# RiseUpBOTTOM.net
KiCad netlist of a schematic drawn in EAGLE
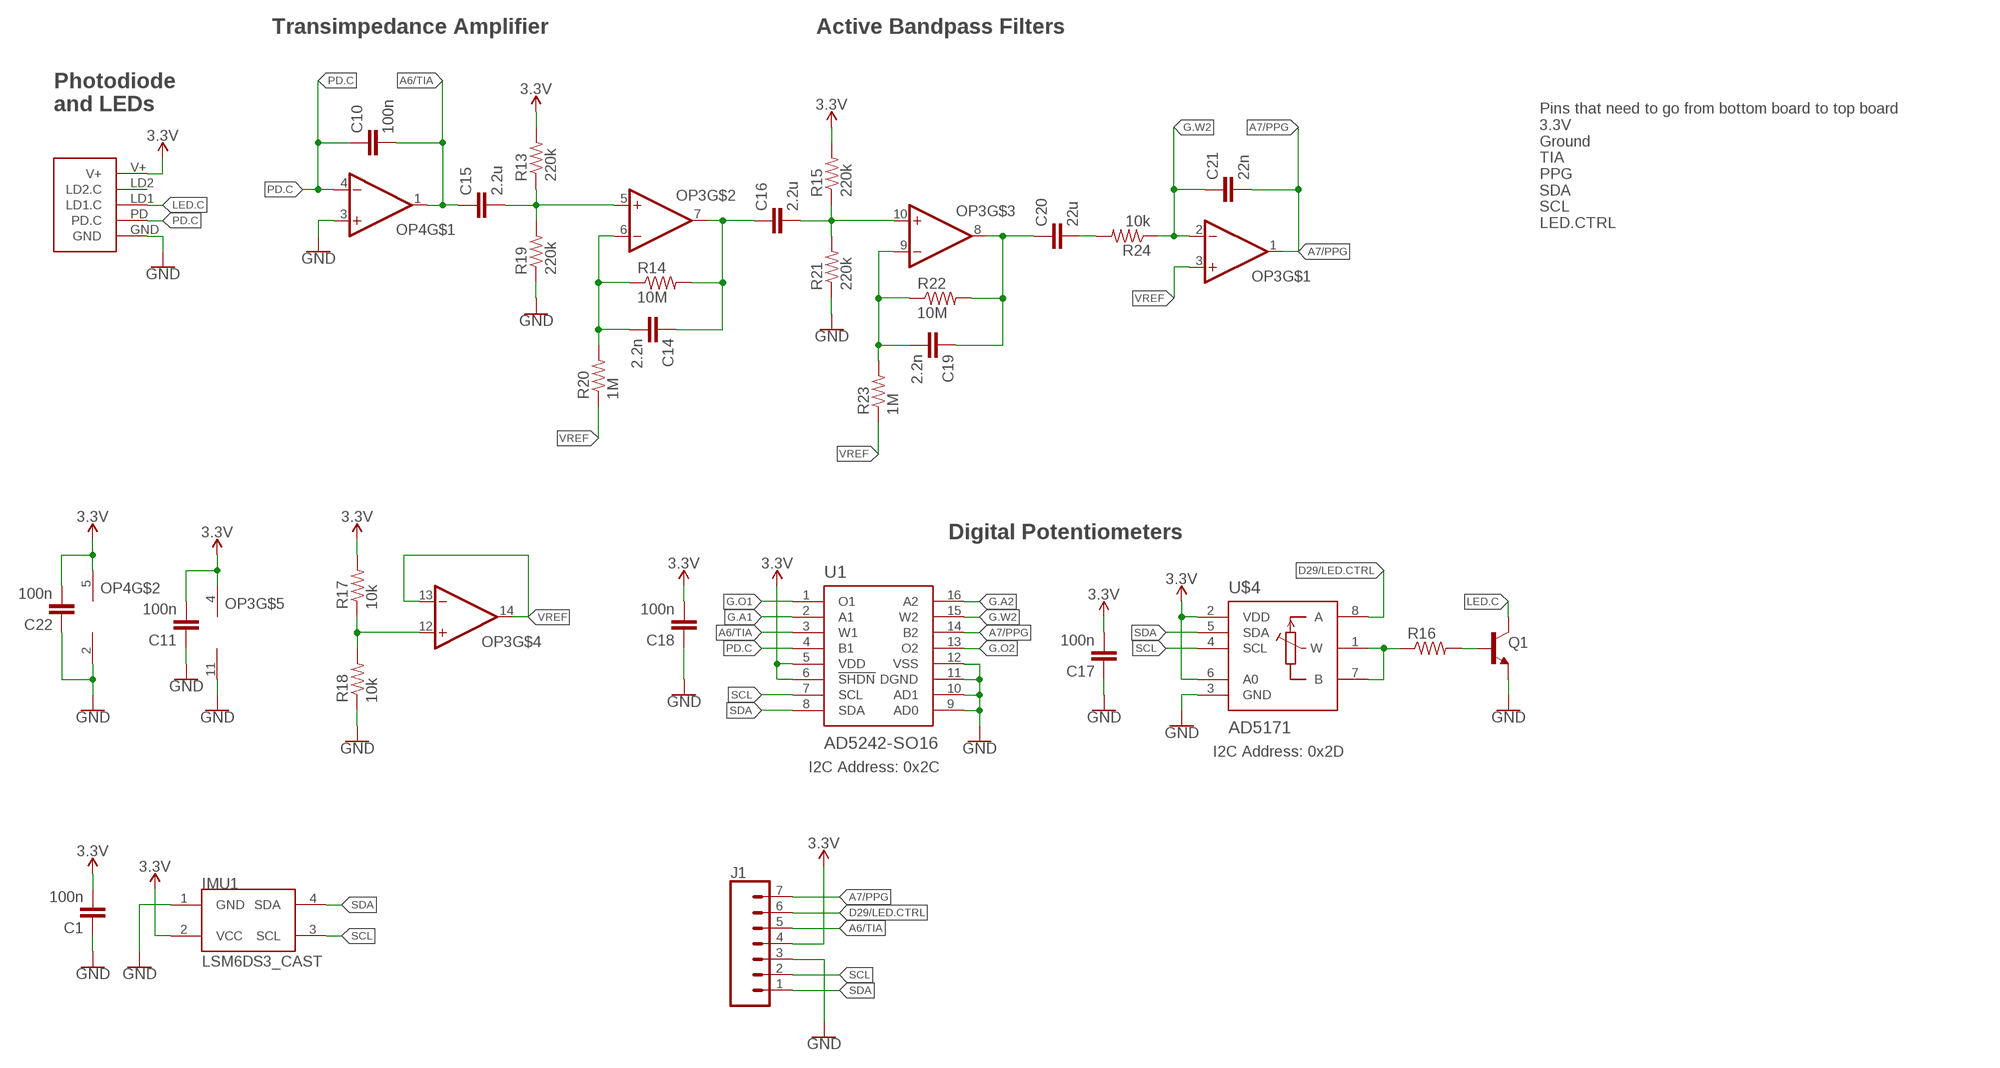
[diagram p0: schematic, sheet 1]

(export (version "E")
  (design (tool "Eeschema 10.0.6"))
  (components
    (comp (ref "C1")
      (value "100n")
      (footprint "eagle-import:C0603")
      (libsource (lib "eagle-import") (part "CAPACITOR0603"))
    )
    (comp (ref "C10")
      (value "100n")
      (footprint "eagle-import:C0603")
      (libsource (lib "eagle-import") (part "CAPACITOR0603"))
    )
    (comp (ref "C11")
      (value "100n")
      (footprint "eagle-import:C0603")
      (libsource (lib "eagle-import") (part "CAPACITOR0603"))
    )
    (comp (ref "C14")
      (value "2.2n")
      (footprint "eagle-import:C0603")
      (libsource (lib "eagle-import") (part "CAPACITOR0603"))
    )
    (comp (ref "C15")
      (value "2.2u")
      (footprint "eagle-import:C0603")
      (libsource (lib "eagle-import") (part "CAPACITOR0603"))
    )
    (comp (ref "C16")
      (value "2.2u")
      (footprint "eagle-import:C0603")
      (libsource (lib "eagle-import") (part "CAPACITOR0603"))
    )
    (comp (ref "C17")
      (value "100n")
      (footprint "eagle-import:C0603")
      (libsource (lib "eagle-import") (part "CAPACITOR0603"))
    )
    (comp (ref "C18")
      (value "100n")
      (footprint "eagle-import:C0603")
      (libsource (lib "eagle-import") (part "CAPACITOR0603"))
    )
    (comp (ref "C19")
      (value "2.2n")
      (footprint "eagle-import:C0603")
      (libsource (lib "eagle-import") (part "CAPACITOR0603"))
    )
    (comp (ref "C20")
      (value "22u")
      (footprint "eagle-import:C0603")
      (libsource (lib "eagle-import") (part "CAPACITOR0603"))
    )
    (comp (ref "C21")
      (value "22n")
      (footprint "eagle-import:C0603")
      (libsource (lib "eagle-import") (part "CAPACITOR0603"))
    )
    (comp (ref "C22")
      (value "100n")
      (footprint "eagle-import:C0603")
      (libsource (lib "eagle-import") (part "CAPACITOR0603"))
    )
    (comp (ref "IMU1")
      (value "LSM6DS3_CAST")
      (footprint "eagle-import:LSM6DS3_CAST")
      (libsource (lib "eagle-import") (part "LSM6DS3_CAST"))
    )
    (comp (ref "J1")
      (value "CONN_07")
      (footprint "eagle-import:1X07")
      (libsource (lib "eagle-import") (part "CONN_07"))
    )
    (comp (ref "OP3")
      (value "OP-QUAD-SO14")
      (footprint "eagle-import:SO14")
      (libsource (lib "eagle-import") (part "OP-QUAD-SO14"))
    )
    (comp (ref "OP4")
      (value "OP-SINGLEOT")
      (footprint "eagle-import:SOT23-5")
      (libsource (lib "eagle-import") (part "OP-SINGLEOT"))
    )
    (comp (ref "Q1")
      (value "NPN-GENERIC")
      (footprint "eagle-import:SOT23-3")
      (libsource (lib "eagle-import") (part "NPN-GENERIC"))
    )
    (comp (ref "R13")
      (value "220k")
      (footprint "eagle-import:R0603")
      (libsource (lib "eagle-import") (part "RESISTOR0603"))
    )
    (comp (ref "R14")
      (value "10M")
      (footprint "eagle-import:R0603")
      (libsource (lib "eagle-import") (part "RESISTOR0603"))
    )
    (comp (ref "R15")
      (value "220k")
      (footprint "eagle-import:R0603")
      (libsource (lib "eagle-import") (part "RESISTOR0603"))
    )
    (comp (ref "R16")
      (value "RESISTOR0603")
      (footprint "eagle-import:R0603")
      (libsource (lib "eagle-import") (part "RESISTOR0603"))
    )
    (comp (ref "R17")
      (value "10k")
      (footprint "eagle-import:R0402")
      (libsource (lib "eagle-import") (part "RESISTOR0402"))
    )
    (comp (ref "R18")
      (value "10k")
      (footprint "eagle-import:R0402")
      (libsource (lib "eagle-import") (part "RESISTOR0402"))
    )
    (comp (ref "R19")
      (value "220k")
      (footprint "eagle-import:R0603")
      (libsource (lib "eagle-import") (part "RESISTOR0603"))
    )
    (comp (ref "R20")
      (value "1M")
      (footprint "eagle-import:R0603")
      (libsource (lib "eagle-import") (part "RESISTOR0603"))
    )
    (comp (ref "R21")
      (value "220k")
      (footprint "eagle-import:R0603")
      (libsource (lib "eagle-import") (part "RESISTOR0603"))
    )
    (comp (ref "R22")
      (value "10M")
      (footprint "eagle-import:R0603")
      (libsource (lib "eagle-import") (part "RESISTOR0603"))
    )
    (comp (ref "R23")
      (value "1M")
      (footprint "eagle-import:R0603")
      (libsource (lib "eagle-import") (part "RESISTOR0603"))
    )
    (comp (ref "R24")
      (value "10k")
      (footprint "eagle-import:R0603")
      (libsource (lib "eagle-import") (part "RESISTOR0603"))
    )
    (comp (ref "U$3")
      (value "PPG.MODULE.2")
      (footprint "eagle-import:PPG.MODULE.2")
      (libsource (lib "eagle-import") (part "PPG.MODULE.2"))
    )
    (comp (ref "U$4")
      (value "AD5171")
      (footprint "eagle-import:SOT-23-8")
      (libsource (lib "eagle-import") (part "AD5171"))
    )
    (comp (ref "U1")
      (value "AD5242-SO16")
      (footprint "eagle-import:SO16")
      (libsource (lib "eagle-import") (part "AD5242-SO16"))
    )
  )
  (nets
    (net (code "1") (name "3.3V") (class "Default")
      (node (ref "C1") (pin "2") (pinfunction "2_2") (pintype "passive"))
      (node (ref "C11") (pin "2") (pinfunction "2_2") (pintype "passive"))
      (node (ref "C17") (pin "2") (pinfunction "2_2") (pintype "passive"))
      (node (ref "C18") (pin "2") (pinfunction "2_2") (pintype "passive"))
      (node (ref "C22") (pin "2") (pinfunction "2_2") (pintype "passive"))
      (node (ref "IMU1") (pin "2") (pinfunction "VCC_2") (pintype "bidirectional"))
      (node (ref "J1") (pin "4") (pinfunction "4_4") (pintype "passive"))
      (node (ref "OP3") (pin "4") (pinfunction "V+_4") (pintype "power_in"))
      (node (ref "OP4") (pin "5") (pinfunction "V+_5") (pintype "power_in"))
      (node (ref "R13") (pin "2") (pinfunction "2_2") (pintype "passive"))
      (node (ref "R15") (pin "2") (pinfunction "2_2") (pintype "passive"))
      (node (ref "R17") (pin "2") (pinfunction "2_2") (pintype "passive"))
      (node (ref "U$3") (pin "V+") (pinfunction "V+_V+") (pintype "bidirectional"))
      (node (ref "U$4") (pin "2") (pinfunction "VDD_2") (pintype "bidirectional"))
      (node (ref "U$4") (pin "6") (pinfunction "A0_6") (pintype "bidirectional"))
      (node (ref "U1") (pin "5") (pinfunction "VDD_5") (pintype "bidirectional"))
      (node (ref "U1") (pin "6") (pinfunction "~{SHDN}_6") (pintype "bidirectional"))
    )
    (net (code "2") (name "A6{slash}TIA") (class "Default")
      (node (ref "C10") (pin "2") (pinfunction "2_2") (pintype "passive"))
      (node (ref "C15") (pin "1") (pinfunction "1_1") (pintype "passive"))
      (node (ref "J1") (pin "5") (pinfunction "5_5") (pintype "passive"))
      (node (ref "OP4") (pin "1") (pinfunction "OUT_1") (pintype "output"))
      (node (ref "U1") (pin "3") (pinfunction "W1_3") (pintype "bidirectional"))
    )
    (net (code "3") (name "A7{slash}PPG") (class "Default")
      (node (ref "C21") (pin "2") (pinfunction "2_2") (pintype "passive"))
      (node (ref "J1") (pin "7") (pinfunction "7_7") (pintype "passive"))
      (node (ref "OP3") (pin "1") (pinfunction "OUT_1") (pintype "output"))
      (node (ref "U1") (pin "14") (pinfunction "B2_14") (pintype "bidirectional"))
    )
    (net (code "4") (name "D29{slash}LED.CTRL") (class "Default")
      (node (ref "J1") (pin "6") (pinfunction "6_6") (pintype "passive"))
      (node (ref "U$4") (pin "8") (pinfunction "A_8") (pintype "bidirectional"))
    )
    (net (code "5") (name "G.A1") (class "Default")
      (node (ref "U1") (pin "2") (pinfunction "A1_2") (pintype "bidirectional"))
    )
    (net (code "6") (name "G.A2") (class "Default")
      (node (ref "U1") (pin "16") (pinfunction "A2_16") (pintype "bidirectional"))
    )
    (net (code "7") (name "G.O1") (class "Default")
      (node (ref "U1") (pin "1") (pinfunction "O1_1") (pintype "bidirectional"))
    )
    (net (code "8") (name "G.O2") (class "Default")
      (node (ref "U1") (pin "13") (pinfunction "O2_13") (pintype "bidirectional"))
    )
    (net (code "9") (name "G.W2") (class "Default")
      (node (ref "C21") (pin "1") (pinfunction "1_1") (pintype "passive"))
      (node (ref "OP3") (pin "2") (pinfunction "-IN_2") (pintype "input"))
      (node (ref "R24") (pin "1") (pinfunction "1_1") (pintype "passive"))
      (node (ref "U1") (pin "15") (pinfunction "W2_15") (pintype "bidirectional"))
    )
    (net (code "10") (name "GND") (class "Default")
      (node (ref "C1") (pin "1") (pinfunction "1_1") (pintype "passive"))
      (node (ref "C11") (pin "1") (pinfunction "1_1") (pintype "passive"))
      (node (ref "C17") (pin "1") (pinfunction "1_1") (pintype "passive"))
      (node (ref "C18") (pin "1") (pinfunction "1_1") (pintype "passive"))
      (node (ref "C22") (pin "1") (pinfunction "1_1") (pintype "passive"))
      (node (ref "IMU1") (pin "1") (pinfunction "GND_1") (pintype "bidirectional"))
      (node (ref "J1") (pin "3") (pinfunction "3_3") (pintype "passive"))
      (node (ref "OP3") (pin "11") (pinfunction "V-_11") (pintype "power_in"))
      (node (ref "OP4") (pin "2") (pinfunction "V-_2") (pintype "power_in"))
      (node (ref "OP4") (pin "3") (pinfunction "+IN_3") (pintype "input"))
      (node (ref "Q1") (pin "2") (pinfunction "E_2") (pintype "passive"))
      (node (ref "R18") (pin "1") (pinfunction "1_1") (pintype "passive"))
      (node (ref "R19") (pin "1") (pinfunction "1_1") (pintype "passive"))
      (node (ref "R21") (pin "1") (pinfunction "1_1") (pintype "passive"))
      (node (ref "U$3") (pin "GND") (pinfunction "GND_GND") (pintype "bidirectional"))
      (node (ref "U$4") (pin "3") (pinfunction "GND_3") (pintype "bidirectional"))
      (node (ref "U1") (pin "10") (pinfunction "AD1_10") (pintype "bidirectional"))
      (node (ref "U1") (pin "11") (pinfunction "DGND_11") (pintype "bidirectional"))
      (node (ref "U1") (pin "12") (pinfunction "VSS_12") (pintype "bidirectional"))
      (node (ref "U1") (pin "9") (pinfunction "AD0_9") (pintype "bidirectional"))
    )
    (net (code "11") (name "LED.C") (class "Default")
      (node (ref "Q1") (pin "3") (pinfunction "C_3") (pintype "passive"))
      (node (ref "U$3") (pin "LD1") (pinfunction "LD1.C_LD1") (pintype "bidirectional"))
    )
    (net (code "12") (name "Net-(C20-Pad2)") (class "Default")
      (node (ref "C20") (pin "2") (pinfunction "2_2") (pintype "passive"))
      (node (ref "R24") (pin "2") (pinfunction "2_2") (pintype "passive"))
    )
    (net (code "13") (name "Net-(OP3B-+IN)") (class "Default")
      (node (ref "C15") (pin "2") (pinfunction "2_2") (pintype "passive"))
      (node (ref "OP3") (pin "5") (pinfunction "+IN_5") (pintype "input"))
      (node (ref "R13") (pin "1") (pinfunction "1_1") (pintype "passive"))
      (node (ref "R19") (pin "2") (pinfunction "2_2") (pintype "passive"))
    )
    (net (code "14") (name "Net-(OP3B--IN)") (class "Default")
      (node (ref "C14") (pin "2") (pinfunction "2_2") (pintype "passive"))
      (node (ref "OP3") (pin "6") (pinfunction "-IN_6") (pintype "input"))
      (node (ref "R14") (pin "1") (pinfunction "1_1") (pintype "passive"))
      (node (ref "R20") (pin "2") (pinfunction "2_2") (pintype "passive"))
    )
    (net (code "15") (name "Net-(OP3B-OUT)") (class "Default")
      (node (ref "C14") (pin "1") (pinfunction "1_1") (pintype "passive"))
      (node (ref "C16") (pin "1") (pinfunction "1_1") (pintype "passive"))
      (node (ref "OP3") (pin "7") (pinfunction "OUT_7") (pintype "output"))
      (node (ref "R14") (pin "2") (pinfunction "2_2") (pintype "passive"))
    )
    (net (code "16") (name "Net-(OP3C-+IN)") (class "Default")
      (node (ref "C16") (pin "2") (pinfunction "2_2") (pintype "passive"))
      (node (ref "OP3") (pin "10") (pinfunction "+IN_10") (pintype "input"))
      (node (ref "R15") (pin "1") (pinfunction "1_1") (pintype "passive"))
      (node (ref "R21") (pin "2") (pinfunction "2_2") (pintype "passive"))
    )
    (net (code "17") (name "Net-(OP3C--IN)") (class "Default")
      (node (ref "C19") (pin "2") (pinfunction "2_2") (pintype "passive"))
      (node (ref "OP3") (pin "9") (pinfunction "-IN_9") (pintype "input"))
      (node (ref "R22") (pin "1") (pinfunction "1_1") (pintype "passive"))
      (node (ref "R23") (pin "2") (pinfunction "2_2") (pintype "passive"))
    )
    (net (code "18") (name "Net-(OP3C-OUT)") (class "Default")
      (node (ref "C19") (pin "1") (pinfunction "1_1") (pintype "passive"))
      (node (ref "C20") (pin "1") (pinfunction "1_1") (pintype "passive"))
      (node (ref "OP3") (pin "8") (pinfunction "OUT_8") (pintype "output"))
      (node (ref "R22") (pin "2") (pinfunction "2_2") (pintype "passive"))
    )
    (net (code "19") (name "Net-(OP3D-+IN)") (class "Default")
      (node (ref "OP3") (pin "12") (pinfunction "+IN_12") (pintype "input"))
      (node (ref "R17") (pin "1") (pinfunction "1_1") (pintype "passive"))
      (node (ref "R18") (pin "2") (pinfunction "2_2") (pintype "passive"))
    )
    (net (code "20") (name "Net-(Q1-B)") (class "Default")
      (node (ref "Q1") (pin "1") (pinfunction "B_1") (pintype "passive"))
      (node (ref "R16") (pin "2") (pinfunction "2_2") (pintype "passive"))
    )
    (net (code "21") (name "Net-(U$4-B)") (class "Default")
      (node (ref "R16") (pin "1") (pinfunction "1_1") (pintype "passive"))
      (node (ref "U$4") (pin "1") (pinfunction "W_1") (pintype "bidirectional"))
      (node (ref "U$4") (pin "7") (pinfunction "B_7") (pintype "bidirectional"))
    )
    (net (code "22") (name "PD.C") (class "Default")
      (node (ref "C10") (pin "1") (pinfunction "1_1") (pintype "passive"))
      (node (ref "OP4") (pin "4") (pinfunction "-IN_4") (pintype "input"))
      (node (ref "U$3") (pin "PD") (pinfunction "PD.C_PD") (pintype "bidirectional"))
      (node (ref "U1") (pin "4") (pinfunction "B1_4") (pintype "bidirectional"))
    )
    (net (code "23") (name "SCL") (class "Default")
      (node (ref "IMU1") (pin "3") (pinfunction "SCL_3") (pintype "bidirectional"))
      (node (ref "J1") (pin "2") (pinfunction "2_2") (pintype "passive"))
      (node (ref "U$4") (pin "4") (pinfunction "SCL_4") (pintype "bidirectional"))
      (node (ref "U1") (pin "7") (pinfunction "SCL_7") (pintype "bidirectional"))
    )
    (net (code "24") (name "SDA") (class "Default")
      (node (ref "IMU1") (pin "4") (pinfunction "SDA_4") (pintype "bidirectional"))
      (node (ref "J1") (pin "1") (pinfunction "1_1") (pintype "passive"))
      (node (ref "U$4") (pin "5") (pinfunction "SDA_5") (pintype "bidirectional"))
      (node (ref "U1") (pin "8") (pinfunction "SDA_8") (pintype "bidirectional"))
    )
    (net (code "25") (name "VREF") (class "Default")
      (node (ref "OP3") (pin "13") (pinfunction "-IN_13") (pintype "input"))
      (node (ref "OP3") (pin "14") (pinfunction "OUT_14") (pintype "output"))
      (node (ref "OP3") (pin "3") (pinfunction "+IN_3") (pintype "input"))
      (node (ref "R20") (pin "1") (pinfunction "1_1") (pintype "passive"))
      (node (ref "R23") (pin "1") (pinfunction "1_1") (pintype "passive"))
    )
    (net (code "26") (name "unconnected-(U$3-LD2.C-PadLD2)") (class "Default")
      (node (ref "U$3") (pin "LD2") (pinfunction "LD2.C_LD2") (pintype "bidirectional"))
    )
  )
)
